# NIRx_EDDC_v03_wide.net
KiCad netlist of a schematic drawn in EAGLE
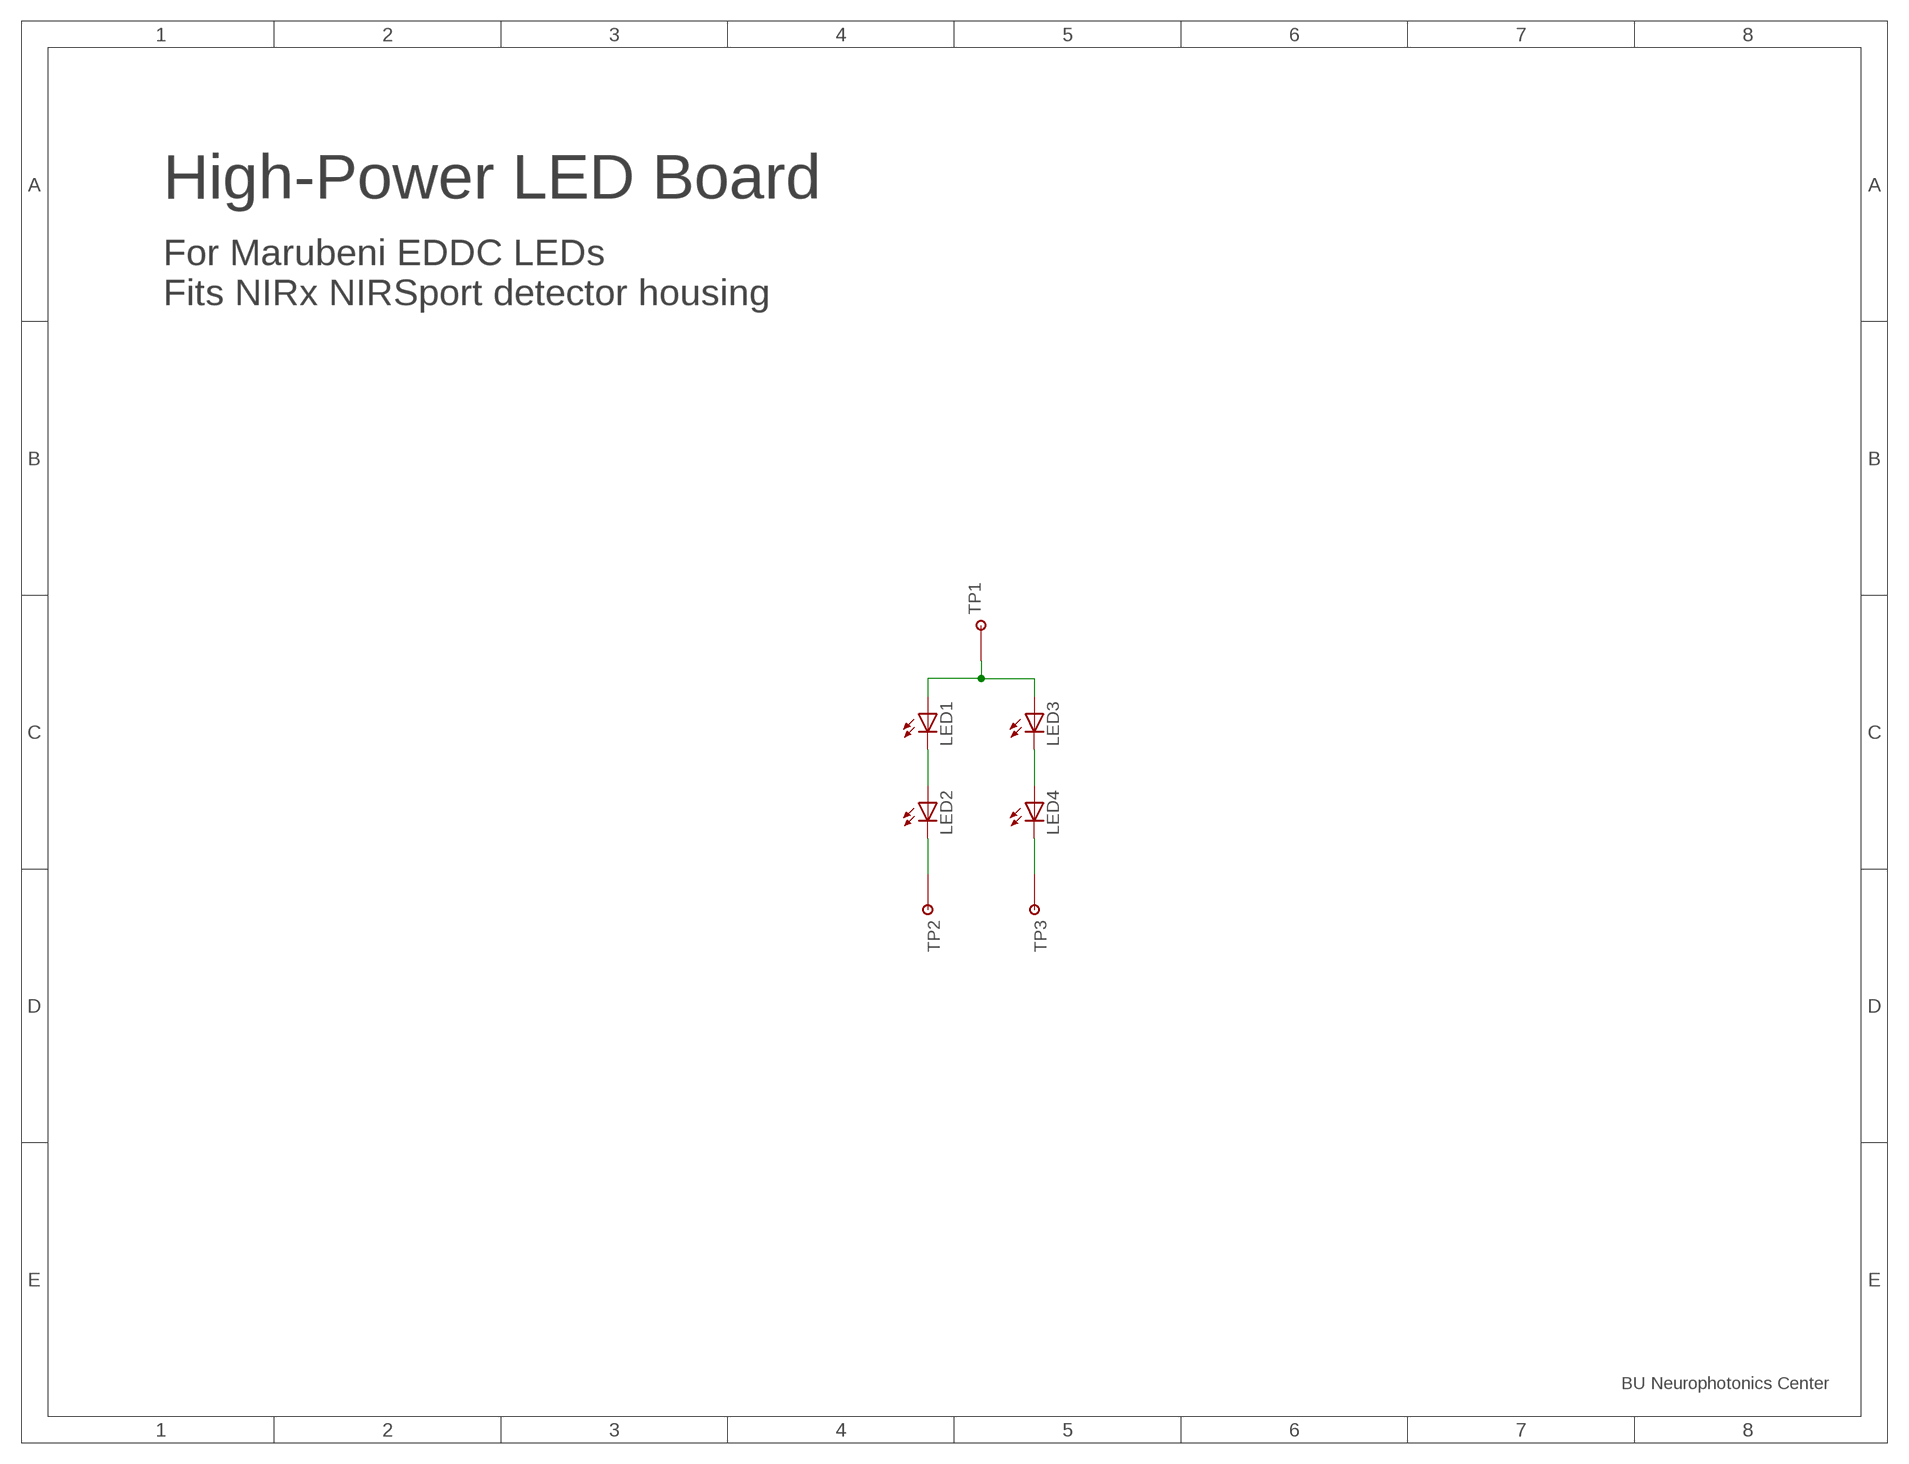
[diagram p0: schematic, sheet 1]

(export (version "E")
  (design (tool "Eeschema 10.0.6"))
  (components
    (comp (ref "LED1")
      (value "LED_EDCC")
      (footprint "eagle-import:MARUBENI_EDCC")
      (libsource (lib "eagle-import") (part "LED_EDCC"))
    )
    (comp (ref "LED2")
      (value "LED_EDCC")
      (footprint "eagle-import:MARUBENI_EDCC")
      (libsource (lib "eagle-import") (part "LED_EDCC"))
    )
    (comp (ref "LED3")
      (value "LED_EDCC")
      (footprint "eagle-import:MARUBENI_EDCC")
      (libsource (lib "eagle-import") (part "LED_EDCC"))
    )
    (comp (ref "LED4")
      (value "LED_EDCC")
      (footprint "eagle-import:MARUBENI_EDCC")
      (libsource (lib "eagle-import") (part "LED_EDCC"))
    )
    (comp (ref "TP1")
      (value "TESTPOINT_PADMEDIUM")
      (footprint "eagle-import:TESTPAD_MEDIUM")
      (libsource (lib "eagle-import") (part "TESTPOINT_PADMEDIUM"))
    )
    (comp (ref "TP2")
      (value "TESTPOINT_PADMEDIUM")
      (footprint "eagle-import:TESTPAD_MEDIUM")
      (libsource (lib "eagle-import") (part "TESTPOINT_PADMEDIUM"))
    )
    (comp (ref "TP3")
      (value "TESTPOINT_PADMEDIUM")
      (footprint "eagle-import:TESTPAD_MEDIUM")
      (libsource (lib "eagle-import") (part "TESTPOINT_PADMEDIUM"))
    )
  )
  (nets
    (net (code "1") (name "Net-(LED1-PadA)") (class "Default")
      (node (ref "LED1") (pin "A") (pinfunction "A_A") (pintype "passive"))
      (node (ref "LED3") (pin "A") (pinfunction "A_A") (pintype "passive"))
      (node (ref "TP1") (pin "P$1") (pinfunction "P$1_P$1") (pintype "bidirectional"))
    )
    (net (code "2") (name "Net-(LED1-PadC)") (class "Default")
      (node (ref "LED1") (pin "C") (pinfunction "C_C") (pintype "passive"))
      (node (ref "LED2") (pin "A") (pinfunction "A_A") (pintype "passive"))
    )
    (net (code "3") (name "Net-(LED2-PadC)") (class "Default")
      (node (ref "LED2") (pin "C") (pinfunction "C_C") (pintype "passive"))
      (node (ref "TP2") (pin "P$1") (pinfunction "P$1_P$1") (pintype "bidirectional"))
    )
    (net (code "4") (name "Net-(LED3-PadC)") (class "Default")
      (node (ref "LED3") (pin "C") (pinfunction "C_C") (pintype "passive"))
      (node (ref "LED4") (pin "A") (pinfunction "A_A") (pintype "passive"))
    )
    (net (code "5") (name "Net-(LED4-PadC)") (class "Default")
      (node (ref "LED4") (pin "C") (pinfunction "C_C") (pintype "passive"))
      (node (ref "TP3") (pin "P$1") (pinfunction "P$1_P$1") (pintype "bidirectional"))
    )
  )
)
